# power.net
KiCad netlist of a schematic drawn in Altium Designer
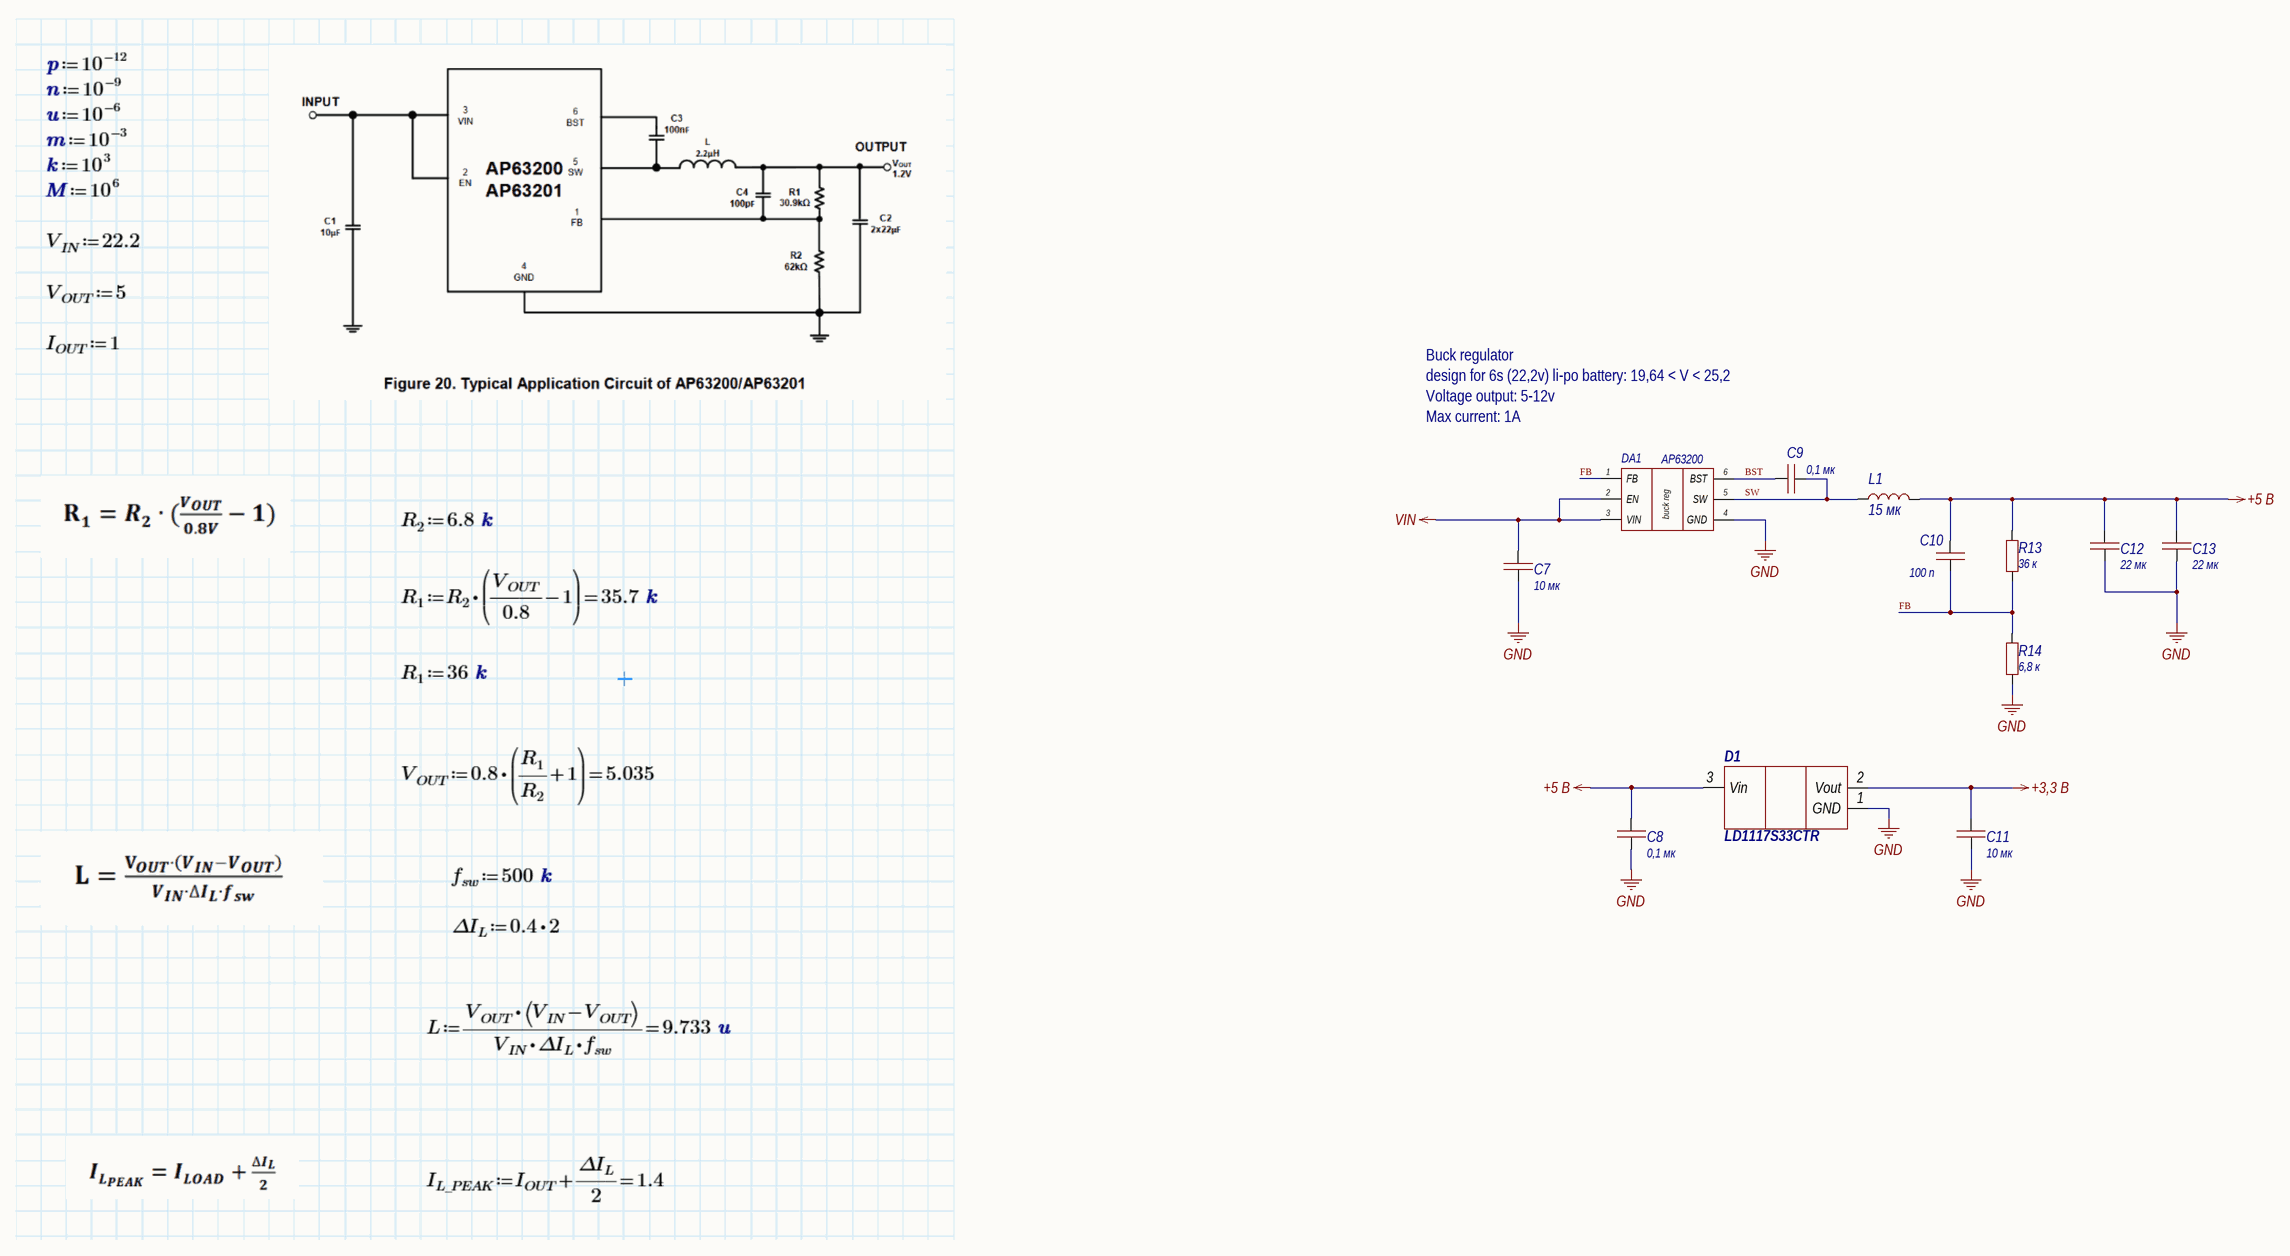
[diagram p0: power.SchDoc]

(export (version "E")
  (design (tool "Eeschema 10.0.6"))
  (components
    (comp (ref "C7")
      (value "10 мк")
      (footprint "1210C")
      (description "Конденсатор 1210C ёмкостью 10 мк 10%, 35 В, X7R")
      (fields (field (name "PART NUMBER") "Capacitor_10u_10_35V_X7R_1210C") (field (name "TOLERANCE") "10%"))
      (libsource (lib "Hydrolib") (part "Capacitor"))
    )
    (comp (ref "C8")
      (value "0,1 мк")
      (footprint "0603C")
      (description "Конденсатор 0603C ёмкостью 0,1 мк 10%, 50 В, X7R")
      (fields (field (name "PART NUMBER") "Capacitor_0,1u_10_50V_X7R_0603C") (field (name "TOLERANCE") "10%"))
      (libsource (lib "Hydrolib") (part "Capacitor"))
    )
    (comp (ref "C9")
      (value "0,1 мк")
      (footprint "0603C")
      (description "Конденсатор 0603C ёмкостью 0,1 мк 10%, 50 В, X7R")
      (fields (field (name "PART NUMBER") "Capacitor_0,1u_10_50V_X7R_0603C") (field (name "TOLERANCE") "10%"))
      (libsource (lib "Hydrolib") (part "Capacitor"))
    )
    (comp (ref "C10")
      (value "100 п")
      (footprint "0603C")
      (description "Конденсатор 0603C ёмкостью 100 п 10%, 50 В, X7R")
      (fields (field (name "PART NUMBER") "Capacitor_100p_10_50V_X7R_0603C") (field (name "TOLERANCE") "10%"))
      (libsource (lib "Hydrolib") (part "Capacitor"))
    )
    (comp (ref "C11")
      (value "10 мк")
      (footprint "1210C")
      (description "Конденсатор 1210C ёмкостью 10 мк 10%, 35 В, X7R")
      (fields (field (name "PART NUMBER") "Capacitor_10u_10_35V_X7R_1210C") (field (name "TOLERANCE") "10%"))
      (libsource (lib "Hydrolib") (part "Capacitor"))
    )
    (comp (ref "C12")
      (value "22 мк")
      (footprint "1210C")
      (description "Конденсатор 1210C ёмкостью 22 мк 10%, 25 В, X7R")
      (fields (field (name "PART NUMBER") "Capacitor_22u_10_25V_X7R_1210C") (field (name "TOLERANCE") "10%"))
      (libsource (lib "Hydrolib") (part "Capacitor"))
    )
    (comp (ref "C13")
      (value "22 мк")
      (footprint "1210C")
      (description "Конденсатор 1210C ёмкостью 22 мк 10%, 25 В, X7R")
      (fields (field (name "PART NUMBER") "Capacitor_22u_10_25V_X7R_1210C") (field (name "TOLERANCE") "10%"))
      (libsource (lib "Hydrolib") (part "Capacitor"))
    )
    (comp (ref "D1")
      (value "LD1117S33CTR")
      (footprint "SOT223")
      (description "Линейный стабилизатор напряжения")
      (libsource (lib "Hydrolib") (part "LD1117S33CTR"))
    )
    (comp (ref "DA1")
      (value "AP63200")
      (footprint "TSOT26")
      (description "DC-DC понижающий преобразователь, Vin: 3.8 - 40 В, adj, 2 А")
      (libsource (lib "Hydrolib") (part "AP63200"))
    )
    (comp (ref "L1")
      (value "15 мк")
      (footprint "SP43")
      (description "Индуктивность на 15 мкГн, номинальный ток 1,3 А")
      (fields (field (name "PART NUMBER") "SP43-150K"))
      (libsource (lib "Hydrolib") (part "Inductance"))
    )
    (comp (ref "R13")
      (value "36 к")
      (footprint "0603R")
      (description "Резистор номиналом 36 кОм 1%")
      (fields (field (name "PART NUMBER") "Resistor_36k_1_0603") (field (name "TOLERANCE") "1%"))
      (libsource (lib "Hydrolib") (part "Resistor"))
    )
    (comp (ref "R14")
      (value "6,8 к")
      (footprint "0603R")
      (description "Резистор номиналом 6,8 кОм 1%")
      (fields (field (name "PART NUMBER") "Resistor_6.8k_1_0603") (field (name "TOLERANCE") "1%"))
      (libsource (lib "Hydrolib") (part "Resistor"))
    )
  )
  (nets
    (net (code "1") (name "+3,3 В") (class "Default")
      (node (ref "C11") (pin "2") (pinfunction "2_2") (pintype "passive"))
      (node (ref "D1") (pin "2") (pinfunction "Vout_2") (pintype "passive"))
    )
    (net (code "2") (name "+5 В") (class "Default")
      (node (ref "C10") (pin "2") (pinfunction "2_2") (pintype "passive"))
      (node (ref "C12") (pin "2") (pinfunction "2_2") (pintype "passive"))
      (node (ref "C13") (pin "2") (pinfunction "2_2") (pintype "passive"))
      (node (ref "C8") (pin "2") (pinfunction "2_2") (pintype "passive"))
      (node (ref "D1") (pin "3") (pinfunction "Vin_3") (pintype "passive"))
      (node (ref "L1") (pin "2") (pinfunction "2_2") (pintype "passive"))
      (node (ref "R13") (pin "2") (pinfunction "2_2") (pintype "passive"))
    )
    (net (code "3") (name "/BST") (class "Default")
      (node (ref "C9") (pin "1") (pinfunction "1_1") (pintype "passive"))
      (node (ref "DA1") (pin "6") (pinfunction "BST_6") (pintype "passive"))
    )
    (net (code "4") (name "/FB") (class "Default")
      (node (ref "C10") (pin "1") (pinfunction "1_1") (pintype "passive"))
      (node (ref "DA1") (pin "1") (pinfunction "FB_1") (pintype "passive"))
      (node (ref "R13") (pin "1") (pinfunction "1_1") (pintype "passive"))
      (node (ref "R14") (pin "2") (pinfunction "2_2") (pintype "passive"))
    )
    (net (code "5") (name "/SW") (class "Default")
      (node (ref "C9") (pin "2") (pinfunction "2_2") (pintype "passive"))
      (node (ref "DA1") (pin "5") (pinfunction "SW_5") (pintype "passive"))
      (node (ref "L1") (pin "1") (pinfunction "1_1") (pintype "passive"))
    )
    (net (code "6") (name "GND") (class "Default")
      (node (ref "C11") (pin "1") (pinfunction "1_1") (pintype "passive"))
      (node (ref "C12") (pin "1") (pinfunction "1_1") (pintype "passive"))
      (node (ref "C13") (pin "1") (pinfunction "1_1") (pintype "passive"))
      (node (ref "C7") (pin "1") (pinfunction "1_1") (pintype "passive"))
      (node (ref "C8") (pin "1") (pinfunction "1_1") (pintype "passive"))
      (node (ref "D1") (pin "1") (pinfunction "GND_1") (pintype "passive"))
      (node (ref "DA1") (pin "4") (pinfunction "GND_4") (pintype "passive"))
      (node (ref "R14") (pin "1") (pinfunction "1_1") (pintype "passive"))
    )
    (net (code "7") (name "VIN") (class "Default")
      (node (ref "C7") (pin "2") (pinfunction "2_2") (pintype "passive"))
      (node (ref "DA1") (pin "2") (pinfunction "EN_2") (pintype "passive"))
      (node (ref "DA1") (pin "3") (pinfunction "VIN_3") (pintype "passive"))
    )
  )
)
